# Sheet1.net
KiCad netlist of a schematic drawn in Altium Designer
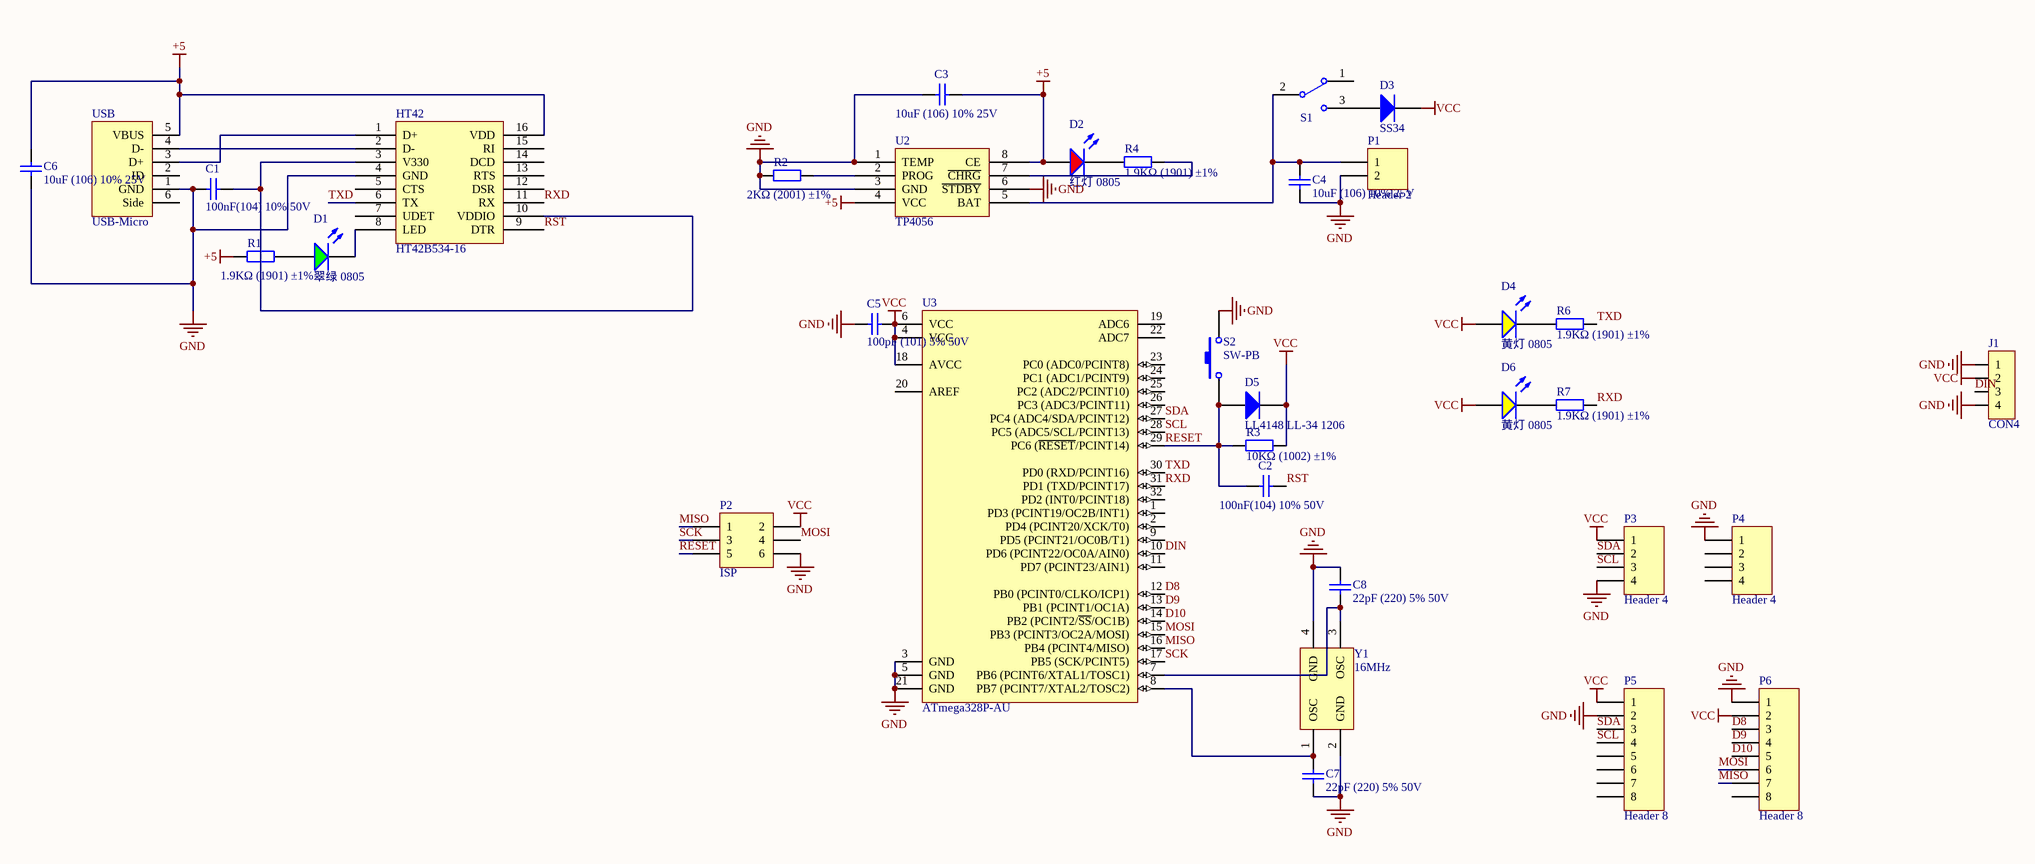
[diagram p0: Sheet1.SchDoc]

(export (version "E")
  (design (tool "Eeschema 10.0.6"))
  (components
    (comp (ref "C1")
      (value "100nF(104) 10% 50V")
      (footprint "0805_C")
      (description "贴片电容")
      (libsource (lib "Miscellaneous Devices LC") (part "0805 100nF(104) 10% 50V"))
    )
    (comp (ref "C2")
      (value "100nF(104) 10% 50V")
      (footprint "0805_C")
      (description "贴片电容")
      (libsource (lib "Miscellaneous Devices LC") (part "0805 100nF(104) 10% 50V"))
    )
    (comp (ref "C3")
      (value "10uF (106) 10% 25V")
      (footprint "0805_C")
      (description "贴片电容")
      (libsource (lib "Miscellaneous Devices LC") (part "0805 10uF (106) 10% 25V"))
    )
    (comp (ref "C4")
      (value "10uF (106) 10% 25V")
      (footprint "0805_C")
      (description "贴片电容")
      (libsource (lib "Miscellaneous Devices LC") (part "0805 10uF (106) 10% 25V"))
    )
    (comp (ref "C5")
      (value "100pF (101) 5% 50V")
      (footprint "0805_C")
      (description "贴片电容")
      (libsource (lib "Miscellaneous Devices LC") (part "0805 100pF (101) 5% 50V"))
    )
    (comp (ref "C6")
      (value "10uF (106) 10% 25V")
      (footprint "0805_C")
      (description "贴片电容")
      (libsource (lib "Miscellaneous Devices LC") (part "0805 10uF (106) 10% 25V"))
    )
    (comp (ref "C7")
      (value "22pF (220) 5% 50V")
      (footprint "0805_C")
      (description "贴片电容")
      (libsource (lib "Miscellaneous Devices LC") (part "0805 22pF (220) 5% 50V"))
    )
    (comp (ref "C8")
      (value "22pF (220) 5% 50V")
      (footprint "0805_C")
      (description "贴片电容")
      (libsource (lib "Miscellaneous Devices LC") (part "0805 22pF (220) 5% 50V"))
    )
    (comp (ref "D1")
      (value "翠绿 0805")
      (footprint "0805_LED_S1")
      (description "发光二极管")
      (libsource (lib "Miscellaneous Devices LC") (part "0805 翠绿"))
    )
    (comp (ref "D2")
      (value "红灯 0805")
      (footprint "0805_LED_S1")
      (description "发光二极管")
      (libsource (lib "Miscellaneous Devices LC") (part "0805 红灯"))
    )
    (comp (ref "D3")
      (value "SS34")
      (footprint "SMA(DO-214AC)_S1")
      (description "二极管")
      (libsource (lib "Miscellaneous Devices LC") (part "SMA(DO-214AC) SS210"))
    )
    (comp (ref "D4")
      (value "黄灯 0805")
      (footprint "0805_LED_S1")
      (description "发光二极管")
      (libsource (lib "Miscellaneous Devices LC") (part "0805 黄灯"))
    )
    (comp (ref "D5")
      (value "LL4148 LL-34 1206")
      (footprint "LL-34")
      (description "开关二极管")
      (libsource (lib "Miscellaneous Devices LC") (part "LL-34 LL4148 LL-34 1206"))
    )
    (comp (ref "D6")
      (value "黄灯 0805")
      (footprint "0805_LED_S1")
      (description "发光二极管")
      (libsource (lib "Miscellaneous Devices LC") (part "0805 黄灯"))
    )
    (comp (ref "HT42")
      (value "HT42B534-16")
      (footprint "SOP-16")
      (description "USB_COM")
      (libsource (lib "Zzz") (part "HT42B534-16"))
    )
    (comp (ref "J1")
      (value "CON4")
      (footprint "XH-4")
      (description "Connector")
      (libsource (lib "连接器件") (part "CON4"))
    )
    (comp (ref "P1")
      (value "Header 2")
      (footprint "HDR1X2")
      (description "Header, 2-Pin")
      (fields (field (name "PUBLISHER") "Altium Limited"))
      (libsource (lib "Miscellaneous Connectors") (part "Header 2"))
    )
    (comp (ref "P2")
      (value "ISP")
      (footprint "HDR2X3")
      (description "Header, 3-Pin, Dual row")
      (fields (field (name "PUBLISHER") "Altium Limited"))
      (libsource (lib "Miscellaneous Connectors") (part "Header 3X2"))
    )
    (comp (ref "P3")
      (value "Header 4")
      (footprint "HDR1X4")
      (description "Header, 4-Pin")
      (fields (field (name "PUBLISHER") "Altium Limited"))
      (libsource (lib "Miscellaneous Connectors") (part "Header 4"))
    )
    (comp (ref "P4")
      (value "Header 4")
      (footprint "HDR1X4")
      (description "Header, 4-Pin")
      (fields (field (name "PUBLISHER") "Altium Limited"))
      (libsource (lib "Miscellaneous Connectors") (part "Header 4"))
    )
    (comp (ref "P5")
      (value "Header 8")
      (footprint "HDR1X8")
      (description "Header, 8-Pin")
      (fields (field (name "PUBLISHER") "Altium Limited"))
      (libsource (lib "Miscellaneous Connectors") (part "Header 8"))
    )
    (comp (ref "P6")
      (value "Header 8")
      (footprint "HDR1X8")
      (description "Header, 8-Pin")
      (fields (field (name "PUBLISHER") "Altium Limited"))
      (libsource (lib "Miscellaneous Connectors") (part "Header 8"))
    )
    (comp (ref "R1")
      (value "1.9KΩ (1901) ±1%")
      (footprint "0805_R")
      (description "贴片电阻")
      (libsource (lib "Miscellaneous Devices LC") (part "0805 1.8KΩ (1801) 1%"))
    )
    (comp (ref "R2")
      (value "2KΩ (2001) ±1%")
      (footprint "0805_R")
      (description "贴片电阻")
      (libsource (lib "Miscellaneous Devices LC") (part "0805 2KΩ (2001) 1%"))
    )
    (comp (ref "R3")
      (value "10KΩ (1002) ±1%")
      (footprint "0805_R")
      (description "贴片电阻")
      (libsource (lib "Miscellaneous Devices LC") (part "0805 10KΩ (1002) 1%"))
    )
    (comp (ref "R4")
      (value "1.9KΩ (1901) ±1%")
      (footprint "0805_R")
      (description "贴片电阻")
      (libsource (lib "Miscellaneous Devices LC") (part "0805 1.8KΩ (1801) 1%"))
    )
    (comp (ref "R6")
      (value "1.9KΩ (1901) ±1%")
      (footprint "0805_R")
      (description "贴片电阻")
      (libsource (lib "Miscellaneous Devices LC") (part "0805 1.5KΩ (1501) 1%"))
    )
    (comp (ref "R7")
      (value "1.9KΩ (1901) ±1%")
      (footprint "0805_R")
      (description "贴片电阻")
      (libsource (lib "Miscellaneous Devices LC") (part "0805 1.5KΩ (1501) 1%"))
    )
    (comp (ref "S1")
      (value "SW")
      (footprint "HDR1X3")
      (description "Switch")
      (fields (field (name "PUBLISHER") "Altium Limited"))
      (libsource (lib "小七的原理图库") (part "SW"))
    )
    (comp (ref "S2")
      (value "SW-PB")
      (footprint "SW_PB2_A1")
      (description "微动开关")
      (fields (field (name "PUBLISHER") "Altium Limited"))
      (libsource (lib "Fszhang") (part "SW-PB"))
    )
    (comp (ref "U2")
      (value "TP4056")
      (footprint "SOP-8_EP_150mil")
      (description "电池电源管理")
      (libsource (lib "Miscellaneous Devices LC") (part "TP4056_[C16581]"))
    )
    (comp (ref "U3")
      (value "ATmega328P-AU")
      (footprint "32A_N")
      (fields (field (name "PUBLISHER") "Altium Limited"))
      (libsource (lib "Atmel Microcontroller 8-Bit megaAVR") (part "ATmega328P-AU"))
    )
    (comp (ref "USB")
      (value "USB-Micro")
      (footprint "USB-Micro B")
      (libsource (lib "小七的原理图库") (part "USB-Micro"))
    )
    (comp (ref "Y1") (value "16MHz") (footprint "X5032") (libsource (lib "小七的原理图库") (part "XTAL_SMD2")))
  )
  (nets
    (net (code "1") (name "+5") (class "Default")
      (node (ref "C3") (pin "2") (pinfunction "2_2") (pintype "passive"))
      (node (ref "C6") (pin "2") (pinfunction "2_2") (pintype "passive"))
      (node (ref "D2") (pin "A") (pinfunction "A_A") (pintype "passive"))
      (node (ref "HT42") (pin "16") (pinfunction "VDD_16") (pintype "passive"))
      (node (ref "R1") (pin "1") (pinfunction "1_1") (pintype "passive"))
      (node (ref "U2") (pin "4") (pinfunction "VCC_4") (pintype "passive"))
      (node (ref "U2") (pin "8") (pinfunction "CE_8") (pintype "passive"))
      (node (ref "USB") (pin "5") (pinfunction "VBUS_5") (pintype "passive"))
    )
    (net (code "2") (name "/D8") (class "Default")
      (node (ref "P6") (pin "3") (pinfunction "3_3") (pintype "passive"))
      (node (ref "U3") (pin "12") (pinfunction "PB0_(PCINT0/CLKO/ICP1)_12") (pintype "bidirectional"))
    )
    (net (code "3") (name "/D9") (class "Default")
      (node (ref "P6") (pin "4") (pinfunction "4_4") (pintype "passive"))
      (node (ref "U3") (pin "13") (pinfunction "PB1_(PCINT1/OC1A)_13") (pintype "bidirectional"))
    )
    (net (code "4") (name "/D10") (class "Default")
      (node (ref "P6") (pin "5") (pinfunction "5_5") (pintype "passive"))
      (node (ref "U3") (pin "14") (pinfunction "PB2_(PCINT2/~{SS}/OC1B)_14") (pintype "bidirectional"))
    )
    (net (code "5") (name "/DIN") (class "Default")
      (node (ref "J1") (pin "3") (pinfunction "3_3") (pintype "passive"))
      (node (ref "U3") (pin "10") (pinfunction "PD6_(PCINT22/OC0A/AIN0)_10") (pintype "bidirectional"))
    )
    (net (code "6") (name "/MISO") (class "Default")
      (node (ref "P2") (pin "1") (pinfunction "1_1") (pintype "passive"))
      (node (ref "P6") (pin "7") (pinfunction "7_7") (pintype "passive"))
      (node (ref "U3") (pin "16") (pinfunction "PB4_(PCINT4/MISO)_16") (pintype "bidirectional"))
    )
    (net (code "7") (name "/MOSI") (class "Default")
      (node (ref "P2") (pin "4") (pinfunction "4_4") (pintype "passive"))
      (node (ref "P6") (pin "6") (pinfunction "6_6") (pintype "passive"))
      (node (ref "U3") (pin "15") (pinfunction "PB3_(PCINT3/OC2A/MOSI)_15") (pintype "bidirectional"))
    )
    (net (code "8") (name "/RESET") (class "Default")
      (node (ref "C2") (pin "1") (pinfunction "1_1") (pintype "passive"))
      (node (ref "D5") (pin "1") (pinfunction "A_1") (pintype "passive"))
      (node (ref "P2") (pin "5") (pinfunction "5_5") (pintype "passive"))
      (node (ref "R3") (pin "1") (pinfunction "1_1") (pintype "passive"))
      (node (ref "S2") (pin "1") (pinfunction "1_1") (pintype "passive"))
      (node (ref "U3") (pin "29") (pinfunction "PC6_(~{RESET}/PCINT14)_29") (pintype "bidirectional"))
    )
    (net (code "9") (name "/RST") (class "Default")
      (node (ref "C2") (pin "2") (pinfunction "2_2") (pintype "passive"))
      (node (ref "HT42") (pin "9") (pinfunction "DTR_9") (pintype "passive"))
    )
    (net (code "10") (name "/RXD") (class "Default")
      (node (ref "HT42") (pin "11") (pinfunction "RX_11") (pintype "passive"))
      (node (ref "R7") (pin "2") (pinfunction "2_2") (pintype "passive"))
      (node (ref "U3") (pin "31") (pinfunction "PD1_(TXD/PCINT17)_31") (pintype "bidirectional"))
    )
    (net (code "11") (name "/SCK") (class "Default")
      (node (ref "P2") (pin "3") (pinfunction "3_3") (pintype "passive"))
      (node (ref "U3") (pin "17") (pinfunction "PB5_(SCK/PCINT5)_17") (pintype "bidirectional"))
    )
    (net (code "12") (name "/SCL") (class "Default")
      (node (ref "P3") (pin "3") (pinfunction "3_3") (pintype "passive"))
      (node (ref "P5") (pin "4") (pinfunction "4_4") (pintype "passive"))
      (node (ref "U3") (pin "28") (pinfunction "PC5_(ADC5/SCL/PCINT13)_28") (pintype "bidirectional"))
    )
    (net (code "13") (name "/SDA") (class "Default")
      (node (ref "P3") (pin "2") (pinfunction "2_2") (pintype "passive"))
      (node (ref "P5") (pin "3") (pinfunction "3_3") (pintype "passive"))
      (node (ref "U3") (pin "27") (pinfunction "PC4_(ADC4/SDA/PCINT12)_27") (pintype "bidirectional"))
    )
    (net (code "14") (name "/TXD") (class "Default")
      (node (ref "HT42") (pin "6") (pinfunction "TX_6") (pintype "passive"))
      (node (ref "R6") (pin "2") (pinfunction "2_2") (pintype "passive"))
      (node (ref "U3") (pin "30") (pinfunction "PD0_(RXD/PCINT16)_30") (pintype "bidirectional"))
    )
    (net (code "15") (name "GND") (class "Default")
      (node (ref "C1") (pin "1") (pinfunction "1_1") (pintype "passive"))
      (node (ref "C3") (pin "1") (pinfunction "1_1") (pintype "passive"))
      (node (ref "C4") (pin "1") (pinfunction "1_1") (pintype "passive"))
      (node (ref "C5") (pin "1") (pinfunction "1_1") (pintype "passive"))
      (node (ref "C6") (pin "1") (pinfunction "1_1") (pintype "passive"))
      (node (ref "C7") (pin "1") (pinfunction "1_1") (pintype "passive"))
      (node (ref "C8") (pin "2") (pinfunction "2_2") (pintype "passive"))
      (node (ref "HT42") (pin "4") (pinfunction "GND_4") (pintype "passive"))
      (node (ref "J1") (pin "1") (pinfunction "1_1") (pintype "passive"))
      (node (ref "J1") (pin "4") (pinfunction "4_4") (pintype "passive"))
      (node (ref "P1") (pin "2") (pinfunction "2_2") (pintype "passive"))
      (node (ref "P2") (pin "6") (pinfunction "6_6") (pintype "passive"))
      (node (ref "P3") (pin "4") (pinfunction "4_4") (pintype "passive"))
      (node (ref "P4") (pin "1") (pinfunction "1_1") (pintype "passive"))
      (node (ref "P5") (pin "2") (pinfunction "2_2") (pintype "passive"))
      (node (ref "P6") (pin "1") (pinfunction "1_1") (pintype "passive"))
      (node (ref "R2") (pin "1") (pinfunction "1_1") (pintype "passive"))
      (node (ref "S2") (pin "2") (pinfunction "2_2") (pintype "passive"))
      (node (ref "U2") (pin "1") (pinfunction "TEMP_1") (pintype "passive"))
      (node (ref "U2") (pin "3") (pinfunction "GND_3") (pintype "passive"))
      (node (ref "U2") (pin "6") (pinfunction "~{STDBY}_6") (pintype "passive"))
      (node (ref "U3") (pin "21") (pinfunction "GND_21") (pintype "power_in"))
      (node (ref "U3") (pin "3") (pinfunction "GND_3") (pintype "power_in"))
      (node (ref "U3") (pin "5") (pinfunction "GND_5") (pintype "power_in"))
      (node (ref "USB") (pin "1") (pinfunction "GND_1") (pintype "passive"))
      (node (ref "Y1") (pin "2") (pinfunction "GND_2") (pintype "passive"))
      (node (ref "Y1") (pin "4") (pinfunction "GND_4") (pintype "passive"))
    )
    (net (code "16") (name "Net-(D1-PadA)") (class "Default")
      (node (ref "D1") (pin "A") (pinfunction "A_A") (pintype "passive"))
      (node (ref "R1") (pin "2") (pinfunction "2_2") (pintype "passive"))
    )
    (net (code "17") (name "Net-(D2-PadK)") (class "Default")
      (node (ref "D2") (pin "K") (pinfunction "K_K") (pintype "passive"))
      (node (ref "R4") (pin "1") (pinfunction "1_1") (pintype "passive"))
    )
    (net (code "18") (name "Net-(D3-A)") (class "Default")
      (node (ref "D3") (pin "1") (pinfunction "A_1") (pintype "passive"))
      (node (ref "S1") (pin "3") (pinfunction "NO1_3") (pintype "passive"))
    )
    (net (code "19") (name "Net-(D4-PadK)") (class "Default")
      (node (ref "D4") (pin "K") (pinfunction "K_K") (pintype "passive"))
      (node (ref "R6") (pin "1") (pinfunction "1_1") (pintype "passive"))
    )
    (net (code "20") (name "Net-(D6-PadK)") (class "Default")
      (node (ref "D6") (pin "K") (pinfunction "K_K") (pintype "passive"))
      (node (ref "R7") (pin "1") (pinfunction "1_1") (pintype "passive"))
    )
    (net (code "21") (name "Net-(HT42-D+)") (class "Default")
      (node (ref "HT42") (pin "1") (pinfunction "D+_1") (pintype "passive"))
      (node (ref "USB") (pin "3") (pinfunction "D+_3") (pintype "passive"))
    )
    (net (code "22") (name "Net-(HT42-D-)") (class "Default")
      (node (ref "HT42") (pin "2") (pinfunction "D-_2") (pintype "passive"))
      (node (ref "USB") (pin "4") (pinfunction "D-_4") (pintype "passive"))
    )
    (net (code "23") (name "Net-(HT42-LED)") (class "Default")
      (node (ref "D1") (pin "K") (pinfunction "K_K") (pintype "passive"))
      (node (ref "HT42") (pin "8") (pinfunction "LED_8") (pintype "passive"))
    )
    (net (code "24") (name "Net-(HT42-V330)") (class "Default")
      (node (ref "C1") (pin "2") (pinfunction "2_2") (pintype "passive"))
      (node (ref "HT42") (pin "10") (pinfunction "VDDIO_10") (pintype "passive"))
      (node (ref "HT42") (pin "3") (pinfunction "V330_3") (pintype "passive"))
    )
    (net (code "25") (name "Net-(S1-COMMON1)") (class "Default")
      (node (ref "C4") (pin "2") (pinfunction "2_2") (pintype "passive"))
      (node (ref "P1") (pin "1") (pinfunction "1_1") (pintype "passive"))
      (node (ref "S1") (pin "2") (pinfunction "COMMON1_2") (pintype "passive"))
      (node (ref "U2") (pin "5") (pinfunction "BAT_5") (pintype "passive"))
    )
    (net (code "26") (name "Net-(U2-PROG)") (class "Default")
      (node (ref "R2") (pin "2") (pinfunction "2_2") (pintype "passive"))
      (node (ref "U2") (pin "2") (pinfunction "PROG_2") (pintype "passive"))
    )
    (net (code "27") (name "Net-(U2-~{CHRG})") (class "Default")
      (node (ref "R4") (pin "2") (pinfunction "2_2") (pintype "passive"))
      (node (ref "U2") (pin "7") (pinfunction "~{CHRG}_7") (pintype "passive"))
    )
    (net (code "28") (name "Net-(U3-PB6_(PCINT6{slash}XTAL1{slash}TOSC1))") (class "Default")
      (node (ref "C8") (pin "1") (pinfunction "1_1") (pintype "passive"))
      (node (ref "U3") (pin "7") (pinfunction "PB6_(PCINT6/XTAL1/TOSC1)_7") (pintype "bidirectional"))
      (node (ref "Y1") (pin "3") (pinfunction "OSC_3") (pintype "passive"))
    )
    (net (code "29") (name "Net-(U3-PB7_(PCINT7{slash}XTAL2{slash}TOSC2))") (class "Default")
      (node (ref "C7") (pin "2") (pinfunction "2_2") (pintype "passive"))
      (node (ref "U3") (pin "8") (pinfunction "PB7_(PCINT7/XTAL2/TOSC2)_8") (pintype "bidirectional"))
      (node (ref "Y1") (pin "1") (pinfunction "OSC_1") (pintype "passive"))
    )
    (net (code "30") (name "VCC") (class "Default")
      (node (ref "C5") (pin "2") (pinfunction "2_2") (pintype "passive"))
      (node (ref "D3") (pin "2") (pinfunction "K_2") (pintype "passive"))
      (node (ref "D4") (pin "A") (pinfunction "A_A") (pintype "passive"))
      (node (ref "D5") (pin "2") (pinfunction "K_2") (pintype "passive"))
      (node (ref "D6") (pin "A") (pinfunction "A_A") (pintype "passive"))
      (node (ref "J1") (pin "2") (pinfunction "2_2") (pintype "passive"))
      (node (ref "P2") (pin "2") (pinfunction "2_2") (pintype "passive"))
      (node (ref "P3") (pin "1") (pinfunction "1_1") (pintype "passive"))
      (node (ref "P5") (pin "1") (pinfunction "1_1") (pintype "passive"))
      (node (ref "P6") (pin "2") (pinfunction "2_2") (pintype "passive"))
      (node (ref "R3") (pin "2") (pinfunction "2_2") (pintype "passive"))
      (node (ref "U3") (pin "18") (pinfunction "AVCC_18") (pintype "power_in"))
      (node (ref "U3") (pin "4") (pinfunction "VCC_4") (pintype "power_in"))
      (node (ref "U3") (pin "6") (pinfunction "VCC_6") (pintype "power_in"))
    )
    (net (code "31") (name "unconnected-(HT42-CTS-Pad5)") (class "Default")
      (node (ref "HT42") (pin "5") (pinfunction "CTS_5") (pintype "passive"))
    )
    (net (code "32") (name "unconnected-(HT42-DCD-Pad14)") (class "Default")
      (node (ref "HT42") (pin "14") (pinfunction "DCD_14") (pintype "passive"))
    )
    (net (code "33") (name "unconnected-(HT42-DSR-Pad12)") (class "Default")
      (node (ref "HT42") (pin "12") (pinfunction "DSR_12") (pintype "passive"))
    )
    (net (code "34") (name "unconnected-(HT42-RI-Pad15)") (class "Default")
      (node (ref "HT42") (pin "15") (pinfunction "RI_15") (pintype "passive"))
    )
    (net (code "35") (name "unconnected-(HT42-RTS-Pad13)") (class "Default")
      (node (ref "HT42") (pin "13") (pinfunction "RTS_13") (pintype "passive"))
    )
    (net (code "36") (name "unconnected-(HT42-UDET-Pad7)") (class "Default")
      (node (ref "HT42") (pin "7") (pinfunction "UDET_7") (pintype "passive"))
    )
    (net (code "37") (name "unconnected-(P4-Pad2)") (class "Default")
      (node (ref "P4") (pin "2") (pinfunction "2_2") (pintype "passive"))
    )
    (net (code "38") (name "unconnected-(P4-Pad3)") (class "Default")
      (node (ref "P4") (pin "3") (pinfunction "3_3") (pintype "passive"))
    )
    (net (code "39") (name "unconnected-(P4-Pad4)") (class "Default")
      (node (ref "P4") (pin "4") (pinfunction "4_4") (pintype "passive"))
    )
    (net (code "40") (name "unconnected-(P5-Pad5)") (class "Default")
      (node (ref "P5") (pin "5") (pinfunction "5_5") (pintype "passive"))
    )
    (net (code "41") (name "unconnected-(P5-Pad6)") (class "Default")
      (node (ref "P5") (pin "6") (pinfunction "6_6") (pintype "passive"))
    )
    (net (code "42") (name "unconnected-(P5-Pad7)") (class "Default")
      (node (ref "P5") (pin "7") (pinfunction "7_7") (pintype "passive"))
    )
    (net (code "43") (name "unconnected-(P5-Pad8)") (class "Default")
      (node (ref "P5") (pin "8") (pinfunction "8_8") (pintype "passive"))
    )
    (net (code "44") (name "unconnected-(P6-Pad8)") (class "Default")
      (node (ref "P6") (pin "8") (pinfunction "8_8") (pintype "passive"))
    )
    (net (code "45") (name "unconnected-(S1-NC1-Pad1)") (class "Default")
      (node (ref "S1") (pin "1") (pinfunction "NC1_1") (pintype "passive"))
    )
    (net (code "46") (name "unconnected-(U3-ADC6-Pad19)") (class "Default")
      (node (ref "U3") (pin "19") (pinfunction "ADC6_19") (pintype "passive"))
    )
    (net (code "47") (name "unconnected-(U3-ADC7-Pad22)") (class "Default")
      (node (ref "U3") (pin "22") (pinfunction "ADC7_22") (pintype "passive"))
    )
    (net (code "48") (name "unconnected-(U3-AREF-Pad20)") (class "Default")
      (node (ref "U3") (pin "20") (pinfunction "AREF_20") (pintype "passive"))
    )
    (net (code "49") (name "unconnected-(U3-PC0_(ADC0{slash}PCINT8)-Pad23)") (class "Default")
      (node (ref "U3") (pin "23") (pinfunction "PC0_(ADC0/PCINT8)_23") (pintype "bidirectional"))
    )
    (net (code "50") (name "unconnected-(U3-PC1_(ADC1{slash}PCINT9)-Pad24)") (class "Default")
      (node (ref "U3") (pin "24") (pinfunction "PC1_(ADC1/PCINT9)_24") (pintype "bidirectional"))
    )
    (net (code "51") (name "unconnected-(U3-PC2_(ADC2{slash}PCINT10)-Pad25)") (class "Default")
      (node (ref "U3") (pin "25") (pinfunction "PC2_(ADC2/PCINT10)_25") (pintype "bidirectional"))
    )
    (net (code "52") (name "unconnected-(U3-PC3_(ADC3{slash}PCINT11)-Pad26)") (class "Default")
      (node (ref "U3") (pin "26") (pinfunction "PC3_(ADC3/PCINT11)_26") (pintype "bidirectional"))
    )
    (net (code "53") (name "unconnected-(U3-PD2_(INT0{slash}PCINT18)-Pad32)") (class "Default")
      (node (ref "U3") (pin "32") (pinfunction "PD2_(INT0/PCINT18)_32") (pintype "bidirectional"))
    )
    (net (code "54") (name "unconnected-(U3-PD3_(PCINT19{slash}OC2B{slash}INT1)-Pad1)") (class "Default")
      (node (ref "U3") (pin "1") (pinfunction "PD3_(PCINT19/OC2B/INT1)_1") (pintype "bidirectional"))
    )
    (net (code "55") (name "unconnected-(U3-PD4_(PCINT20{slash}XCK{slash}T0)-Pad2)") (class "Default")
      (node (ref "U3") (pin "2") (pinfunction "PD4_(PCINT20/XCK/T0)_2") (pintype "bidirectional"))
    )
    (net (code "56") (name "unconnected-(U3-PD5_(PCINT21{slash}OC0B{slash}T1)-Pad9)") (class "Default")
      (node (ref "U3") (pin "9") (pinfunction "PD5_(PCINT21/OC0B/T1)_9") (pintype "bidirectional"))
    )
    (net (code "57") (name "unconnected-(U3-PD7_(PCINT23{slash}AIN1)-Pad11)") (class "Default")
      (node (ref "U3") (pin "11") (pinfunction "PD7_(PCINT23/AIN1)_11") (pintype "bidirectional"))
    )
    (net (code "58") (name "unconnected-(USB-ID-Pad2)") (class "Default")
      (node (ref "USB") (pin "2") (pinfunction "ID_2") (pintype "passive"))
    )
    (net (code "59") (name "unconnected-(USB-Side-Pad6)") (class "Default")
      (node (ref "USB") (pin "6") (pinfunction "Side_6") (pintype "passive"))
    )
  )
)
